# LA_16CH.net
KiCad netlist of a schematic drawn in EAGLE
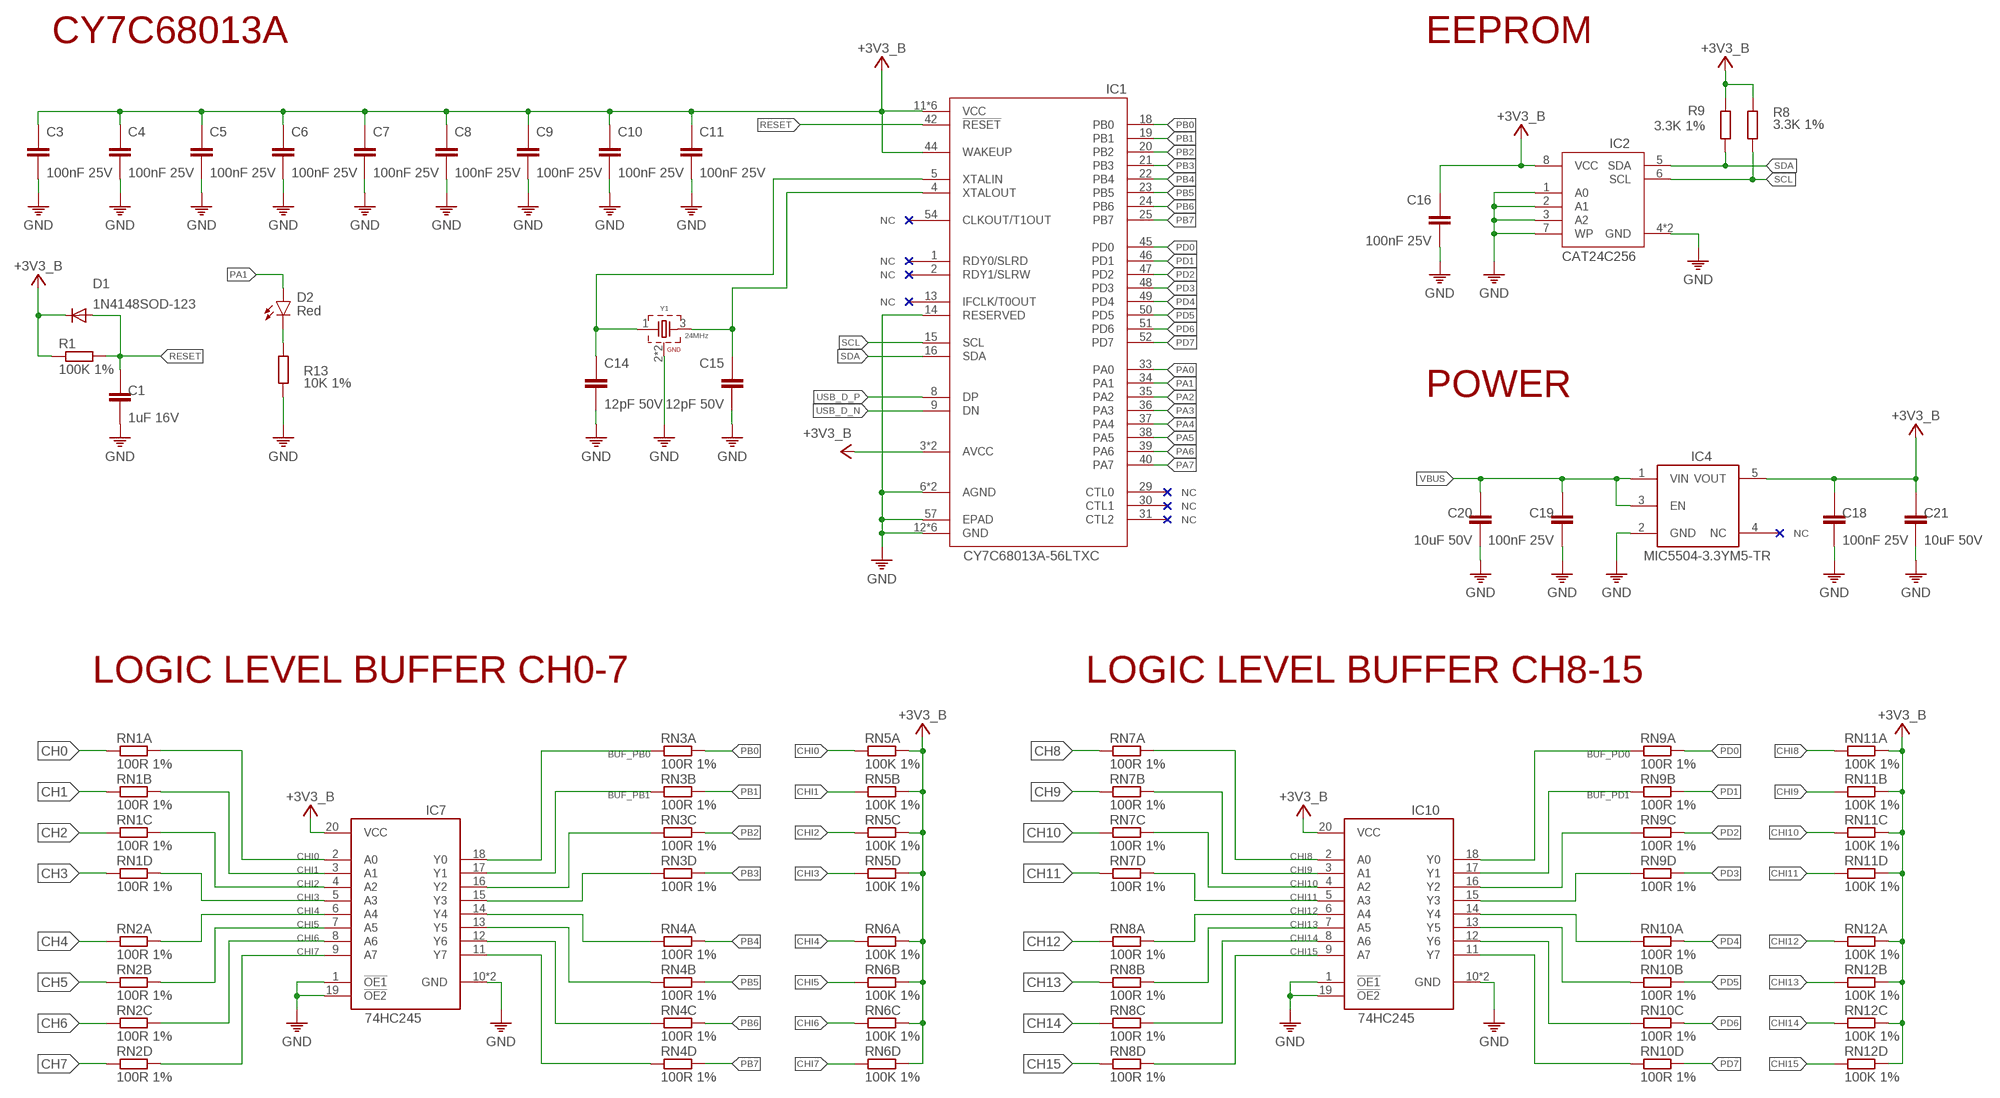
[diagram p0: schematic, sheet 1]

(export (version "E")
  (design (tool "Eeschema 10.0.6"))
  (components
    (comp (ref "C1")
      (value "1uF 16V")
      (footprint "eagle-import:0201")
      (fields (field (name "LCSC_PART") "C307385"))
      (libsource (lib "eagle-import") (part "1UF-16V0201"))
    )
    (comp (ref "C3")
      (value "100nF 25V")
      (footprint "eagle-import:0201")
      (fields (field (name "LCSC_PART") "C76939"))
      (libsource (lib "eagle-import") (part "100NF-25V-0201"))
    )
    (comp (ref "C4")
      (value "100nF 25V")
      (footprint "eagle-import:0201")
      (fields (field (name "LCSC_PART") "C76939"))
      (libsource (lib "eagle-import") (part "100NF-25V-0201"))
    )
    (comp (ref "C5")
      (value "100nF 25V")
      (footprint "eagle-import:0201")
      (fields (field (name "LCSC_PART") "C76939"))
      (libsource (lib "eagle-import") (part "100NF-25V-0201"))
    )
    (comp (ref "C6")
      (value "100nF 25V")
      (footprint "eagle-import:0201")
      (fields (field (name "LCSC_PART") "C76939"))
      (libsource (lib "eagle-import") (part "100NF-25V-0201"))
    )
    (comp (ref "C7")
      (value "100nF 25V")
      (footprint "eagle-import:0201")
      (fields (field (name "LCSC_PART") "C76939"))
      (libsource (lib "eagle-import") (part "100NF-25V-0201"))
    )
    (comp (ref "C8")
      (value "100nF 25V")
      (footprint "eagle-import:0201")
      (fields (field (name "LCSC_PART") "C76939"))
      (libsource (lib "eagle-import") (part "100NF-25V-0201"))
    )
    (comp (ref "C9")
      (value "100nF 25V")
      (footprint "eagle-import:0201")
      (fields (field (name "LCSC_PART") "C76939"))
      (libsource (lib "eagle-import") (part "100NF-25V-0201"))
    )
    (comp (ref "C10")
      (value "100nF 25V")
      (footprint "eagle-import:0201")
      (fields (field (name "LCSC_PART") "C76939"))
      (libsource (lib "eagle-import") (part "100NF-25V-0201"))
    )
    (comp (ref "C11")
      (value "100nF 25V")
      (footprint "eagle-import:0201")
      (fields (field (name "LCSC_PART") "C76939"))
      (libsource (lib "eagle-import") (part "100NF-25V-0201"))
    )
    (comp (ref "C14")
      (value "12pF 50V")
      (footprint "eagle-import:0201")
      (fields (field (name "LCSC_PART") "C50391"))
      (libsource (lib "eagle-import") (part "12PF-50V0201"))
    )
    (comp (ref "C15")
      (value "12pF 50V")
      (footprint "eagle-import:0201")
      (fields (field (name "LCSC_PART") "C50391"))
      (libsource (lib "eagle-import") (part "12PF-50V0201"))
    )
    (comp (ref "C16")
      (value "100nF 25V")
      (footprint "eagle-import:0201")
      (fields (field (name "LCSC_PART") "C76939"))
      (libsource (lib "eagle-import") (part "100NF-25V-0201"))
    )
    (comp (ref "C18")
      (value "100nF 25V")
      (footprint "eagle-import:0201")
      (fields (field (name "LCSC_PART") "C76939"))
      (libsource (lib "eagle-import") (part "100NF-25V-0201"))
    )
    (comp (ref "C19")
      (value "100nF 25V")
      (footprint "eagle-import:0201")
      (fields (field (name "LCSC_PART") "C76939"))
      (libsource (lib "eagle-import") (part "100NF-25V-0201"))
    )
    (comp (ref "C20")
      (value "10uF 50V")
      (footprint "eagle-import:0805")
      (fields (field (name "LCSC_PART") "C440198"))
      (libsource (lib "eagle-import") (part "10UF-50V-0805"))
    )
    (comp (ref "C21")
      (value "10uF 50V")
      (footprint "eagle-import:0805")
      (fields (field (name "LCSC_PART") "C440198"))
      (libsource (lib "eagle-import") (part "10UF-50V-0805"))
    )
    (comp (ref "D1")
      (value "1N4148SOD-123")
      (footprint "eagle-import:SOD-123FL")
      (libsource (lib "eagle-import") (part "DIODE_SOD-123FL"))
    )
    (comp (ref "D2")
      (value "Red")
      (footprint "eagle-import:LED-0603")
      (fields (field (name "LCSC_PART") "C2286"))
      (libsource (lib "eagle-import") (part "LED-REDLED-0603"))
    )
    (comp (ref "IC1")
      (value "CY7C68013A-56LTXC")
      (footprint "eagle-import:QFN50P800X800X100-57T665")
      (libsource (lib "eagle-import") (part "CY7C68013A-56QFNLFXC"))
    )
    (comp (ref "IC2")
      (value "CAT24C256HU4IGT3")
      (footprint "eagle-import:SON50P300X200X50-9T130X140N")
      (libsource (lib "eagle-import") (part "CAT24C256-HU4"))
    )
    (comp (ref "IC4")
      (value "MIC5504-3.3YM5-TR")
      (footprint "eagle-import:SOT23-5")
      (libsource (lib "eagle-import") (part "MIC5504-3.3YM5-TR"))
    )
    (comp (ref "IC7")
      (value "SN74LVC541ARGYR")
      (footprint "eagle-import:QFN50P350X450X100-25T305X205N")
      (libsource (lib "eagle-import") (part "74LVC541A"))
    )
    (comp (ref "IC10")
      (value "SN74LVC541ARGYR")
      (footprint "eagle-import:QFN50P350X450X100-25T305X205N")
      (libsource (lib "eagle-import") (part "74LVC541A"))
    )
    (comp (ref "R1")
      (value "100K 1%")
      (footprint "eagle-import:0201")
      (fields (field (name "LCSC_PART") "C270364"))
      (libsource (lib "eagle-import") (part "100K-1%0201"))
    )
    (comp (ref "R8")
      (value "3.3K 1%")
      (footprint "eagle-import:0201")
      (fields (field (name "LCSC_PART") "C270350"))
      (libsource (lib "eagle-import") (part "3.3K-1%0201"))
    )
    (comp (ref "R9")
      (value "3.3K 1%")
      (footprint "eagle-import:0201")
      (fields (field (name "LCSC_PART") "C270350"))
      (libsource (lib "eagle-import") (part "3.3K-1%0201"))
    )
    (comp (ref "R13")
      (value "10K 1%")
      (footprint "eagle-import:0603")
      (fields (field (name "LCSC_PART") "C25804"))
      (libsource (lib "eagle-import") (part "10K-1%0603"))
    )
    (comp (ref "RN1")
      (value "100R 1%")
      (footprint "eagle-import:0603X4-1206")
      (fields (field (name "LCSC_PART") "C136838"))
      (libsource (lib "eagle-import") (part "100R-1%_ARRAY0603X4-1206"))
    )
    (comp (ref "RN2")
      (value "100R 1%")
      (footprint "eagle-import:0603X4-1206")
      (fields (field (name "LCSC_PART") "C136838"))
      (libsource (lib "eagle-import") (part "100R-1%_ARRAY0603X4-1206"))
    )
    (comp (ref "RN3")
      (value "100R 1%")
      (footprint "eagle-import:0603X4-1206")
      (fields (field (name "LCSC_PART") "C136838"))
      (libsource (lib "eagle-import") (part "100R-1%_ARRAY0603X4-1206"))
    )
    (comp (ref "RN4")
      (value "100R 1%")
      (footprint "eagle-import:0603X4-1206")
      (fields (field (name "LCSC_PART") "C136838"))
      (libsource (lib "eagle-import") (part "100R-1%_ARRAY0603X4-1206"))
    )
    (comp (ref "RN5")
      (value "100K 1%")
      (footprint "eagle-import:0603X4-1206")
      (fields (field (name "LCSC_PART") "C110374"))
      (libsource (lib "eagle-import") (part "100K-1%_ARRAY0603X4-1206"))
    )
    (comp (ref "RN6")
      (value "100K 1%")
      (footprint "eagle-import:0603X4-1206")
      (fields (field (name "LCSC_PART") "C110374"))
      (libsource (lib "eagle-import") (part "100K-1%_ARRAY0603X4-1206"))
    )
    (comp (ref "RN7")
      (value "100R 1%")
      (footprint "eagle-import:0603X4-1206")
      (fields (field (name "LCSC_PART") "C136838"))
      (libsource (lib "eagle-import") (part "100R-1%_ARRAY0603X4-1206"))
    )
    (comp (ref "RN8")
      (value "100R 1%")
      (footprint "eagle-import:0603X4-1206")
      (fields (field (name "LCSC_PART") "C136838"))
      (libsource (lib "eagle-import") (part "100R-1%_ARRAY0603X4-1206"))
    )
    (comp (ref "RN9")
      (value "100R 1%")
      (footprint "eagle-import:0603X4-1206")
      (fields (field (name "LCSC_PART") "C136838"))
      (libsource (lib "eagle-import") (part "100R-1%_ARRAY0603X4-1206"))
    )
    (comp (ref "RN10")
      (value "100R 1%")
      (footprint "eagle-import:0603X4-1206")
      (fields (field (name "LCSC_PART") "C136838"))
      (libsource (lib "eagle-import") (part "100R-1%_ARRAY0603X4-1206"))
    )
    (comp (ref "RN11")
      (value "100K 1%")
      (footprint "eagle-import:0603X4-1206")
      (fields (field (name "LCSC_PART") "C110374"))
      (libsource (lib "eagle-import") (part "100K-1%_ARRAY0603X4-1206"))
    )
    (comp (ref "RN12")
      (value "100K 1%")
      (footprint "eagle-import:0603X4-1206")
      (fields (field (name "LCSC_PART") "C110374"))
      (libsource (lib "eagle-import") (part "100K-1%_ARRAY0603X4-1206"))
    )
    (comp (ref "Y1")
      (value "24MHz")
      (footprint "eagle-import:WE-XTAL_CFPX-180")
      (fields (field (name "TOLERANCE") "±10ppm"))
      (libsource (lib "eagle-import") (part "WE-XTAL_CFPX-180_830058149"))
    )
  )
  (nets
    (net (code "1") (name "+3V3_B") (class "Default")
      (node (ref "C10") (pin "1") (pinfunction "1_1") (pintype "passive"))
      (node (ref "C11") (pin "1") (pinfunction "1_1") (pintype "passive"))
      (node (ref "C16") (pin "1") (pinfunction "1_1") (pintype "passive"))
      (node (ref "C18") (pin "1") (pinfunction "1_1") (pintype "passive"))
      (node (ref "C21") (pin "1") (pinfunction "1_1") (pintype "passive"))
      (node (ref "C3") (pin "1") (pinfunction "1_1") (pintype "passive"))
      (node (ref "C4") (pin "1") (pinfunction "1_1") (pintype "passive"))
      (node (ref "C5") (pin "1") (pinfunction "1_1") (pintype "passive"))
      (node (ref "C6") (pin "1") (pinfunction "1_1") (pintype "passive"))
      (node (ref "C7") (pin "1") (pinfunction "1_1") (pintype "passive"))
      (node (ref "C8") (pin "1") (pinfunction "1_1") (pintype "passive"))
      (node (ref "C9") (pin "1") (pinfunction "1_1") (pintype "passive"))
      (node (ref "D1") (pin "C") (pinfunction "C_C") (pintype "passive"))
      (node (ref "IC1") (pin "11") (pinfunction "VCC_11") (pintype "power_in"))
      (node (ref "IC1") (pin "17") (pinfunction "VCC_17") (pintype "power_in"))
      (node (ref "IC1") (pin "27") (pinfunction "VCC_27") (pintype "power_in"))
      (node (ref "IC1") (pin "3") (pinfunction "AVCC_3") (pintype "power_in"))
      (node (ref "IC1") (pin "32") (pinfunction "VCC_32") (pintype "power_in"))
      (node (ref "IC1") (pin "43") (pinfunction "VCC_43") (pintype "power_in"))
      (node (ref "IC1") (pin "44") (pinfunction "WAKEUP_44") (pintype "input"))
      (node (ref "IC1") (pin "55") (pinfunction "VCC_55") (pintype "power_in"))
      (node (ref "IC1") (pin "7") (pinfunction "AVCC_7") (pintype "power_in"))
      (node (ref "IC10") (pin "20") (pinfunction "VCC_20") (pintype "power_in"))
      (node (ref "IC2") (pin "8") (pinfunction "VCC_8") (pintype "power_in"))
      (node (ref "IC4") (pin "5") (pinfunction "VOUT_5") (pintype "bidirectional"))
      (node (ref "IC7") (pin "20") (pinfunction "VCC_20") (pintype "power_in"))
      (node (ref "R1") (pin "1") (pinfunction "1_1") (pintype "passive"))
      (node (ref "R8") (pin "2") (pinfunction "2_2") (pintype "passive"))
      (node (ref "R9") (pin "2") (pinfunction "2_2") (pintype "passive"))
      (node (ref "RN11") (pin "A2") (pinfunction "2_A2") (pintype "passive"))
      (node (ref "RN11") (pin "B2") (pinfunction "2_B2") (pintype "passive"))
      (node (ref "RN11") (pin "C2") (pinfunction "2_C2") (pintype "passive"))
      (node (ref "RN11") (pin "D2") (pinfunction "2_D2") (pintype "passive"))
      (node (ref "RN12") (pin "A2") (pinfunction "2_A2") (pintype "passive"))
      (node (ref "RN12") (pin "B2") (pinfunction "2_B2") (pintype "passive"))
      (node (ref "RN12") (pin "C2") (pinfunction "2_C2") (pintype "passive"))
      (node (ref "RN12") (pin "D2") (pinfunction "2_D2") (pintype "passive"))
      (node (ref "RN5") (pin "A2") (pinfunction "2_A2") (pintype "passive"))
      (node (ref "RN5") (pin "B2") (pinfunction "2_B2") (pintype "passive"))
      (node (ref "RN5") (pin "C2") (pinfunction "2_C2") (pintype "passive"))
      (node (ref "RN5") (pin "D2") (pinfunction "2_D2") (pintype "passive"))
      (node (ref "RN6") (pin "A2") (pinfunction "2_A2") (pintype "passive"))
      (node (ref "RN6") (pin "B2") (pinfunction "2_B2") (pintype "passive"))
      (node (ref "RN6") (pin "C2") (pinfunction "2_C2") (pintype "passive"))
      (node (ref "RN6") (pin "D2") (pinfunction "2_D2") (pintype "passive"))
    )
    (net (code "2") (name "/BUF_PB0") (class "Default")
      (node (ref "IC7") (pin "18") (pinfunction "Y0_18") (pintype "bidirectional"))
      (node (ref "RN3") (pin "A1") (pinfunction "1_A1") (pintype "passive"))
    )
    (net (code "3") (name "/BUF_PB1") (class "Default")
      (node (ref "IC7") (pin "17") (pinfunction "Y1_17") (pintype "bidirectional"))
      (node (ref "RN3") (pin "B1") (pinfunction "1_B1") (pintype "passive"))
    )
    (net (code "4") (name "/BUF_PD0") (class "Default")
      (node (ref "IC10") (pin "18") (pinfunction "Y0_18") (pintype "bidirectional"))
      (node (ref "RN9") (pin "A1") (pinfunction "1_A1") (pintype "passive"))
    )
    (net (code "5") (name "/BUF_PD1") (class "Default")
      (node (ref "IC10") (pin "17") (pinfunction "Y1_17") (pintype "bidirectional"))
      (node (ref "RN9") (pin "B1") (pinfunction "1_B1") (pintype "passive"))
    )
    (net (code "6") (name "CH0") (class "Default")
      (node (ref "RN1") (pin "A1") (pinfunction "1_A1") (pintype "passive"))
    )
    (net (code "7") (name "CH1") (class "Default")
      (node (ref "RN1") (pin "B1") (pinfunction "1_B1") (pintype "passive"))
    )
    (net (code "8") (name "CH2") (class "Default")
      (node (ref "RN1") (pin "C1") (pinfunction "1_C1") (pintype "passive"))
    )
    (net (code "9") (name "CH3") (class "Default")
      (node (ref "RN1") (pin "D1") (pinfunction "1_D1") (pintype "passive"))
    )
    (net (code "10") (name "CH4") (class "Default")
      (node (ref "RN2") (pin "A1") (pinfunction "1_A1") (pintype "passive"))
    )
    (net (code "11") (name "CH5") (class "Default")
      (node (ref "RN2") (pin "B1") (pinfunction "1_B1") (pintype "passive"))
    )
    (net (code "12") (name "CH6") (class "Default")
      (node (ref "RN2") (pin "C1") (pinfunction "1_C1") (pintype "passive"))
    )
    (net (code "13") (name "CH7") (class "Default")
      (node (ref "RN2") (pin "D1") (pinfunction "1_D1") (pintype "passive"))
    )
    (net (code "14") (name "CH8") (class "Default")
      (node (ref "RN7") (pin "A1") (pinfunction "1_A1") (pintype "passive"))
    )
    (net (code "15") (name "CH9") (class "Default")
      (node (ref "RN7") (pin "B1") (pinfunction "1_B1") (pintype "passive"))
    )
    (net (code "16") (name "CH10") (class "Default")
      (node (ref "RN7") (pin "C1") (pinfunction "1_C1") (pintype "passive"))
    )
    (net (code "17") (name "CH11") (class "Default")
      (node (ref "RN7") (pin "D1") (pinfunction "1_D1") (pintype "passive"))
    )
    (net (code "18") (name "CH12") (class "Default")
      (node (ref "RN8") (pin "A1") (pinfunction "1_A1") (pintype "passive"))
    )
    (net (code "19") (name "CH13") (class "Default")
      (node (ref "RN8") (pin "B1") (pinfunction "1_B1") (pintype "passive"))
    )
    (net (code "20") (name "CH14") (class "Default")
      (node (ref "RN8") (pin "C1") (pinfunction "1_C1") (pintype "passive"))
    )
    (net (code "21") (name "CH15") (class "Default")
      (node (ref "RN8") (pin "D1") (pinfunction "1_D1") (pintype "passive"))
    )
    (net (code "22") (name "CHI0") (class "Default")
      (node (ref "IC7") (pin "2") (pinfunction "A0_2") (pintype "bidirectional"))
      (node (ref "RN1") (pin "A2") (pinfunction "2_A2") (pintype "passive"))
      (node (ref "RN5") (pin "A1") (pinfunction "1_A1") (pintype "passive"))
    )
    (net (code "23") (name "CHI1") (class "Default")
      (node (ref "IC7") (pin "3") (pinfunction "A1_3") (pintype "bidirectional"))
      (node (ref "RN1") (pin "B2") (pinfunction "2_B2") (pintype "passive"))
      (node (ref "RN5") (pin "B1") (pinfunction "1_B1") (pintype "passive"))
    )
    (net (code "24") (name "CHI2") (class "Default")
      (node (ref "IC7") (pin "4") (pinfunction "A2_4") (pintype "bidirectional"))
      (node (ref "RN1") (pin "C2") (pinfunction "2_C2") (pintype "passive"))
      (node (ref "RN5") (pin "C1") (pinfunction "1_C1") (pintype "passive"))
    )
    (net (code "25") (name "CHI3") (class "Default")
      (node (ref "IC7") (pin "5") (pinfunction "A3_5") (pintype "bidirectional"))
      (node (ref "RN1") (pin "D2") (pinfunction "2_D2") (pintype "passive"))
      (node (ref "RN5") (pin "D1") (pinfunction "1_D1") (pintype "passive"))
    )
    (net (code "26") (name "CHI4") (class "Default")
      (node (ref "IC7") (pin "6") (pinfunction "A4_6") (pintype "bidirectional"))
      (node (ref "RN2") (pin "A2") (pinfunction "2_A2") (pintype "passive"))
      (node (ref "RN6") (pin "A1") (pinfunction "1_A1") (pintype "passive"))
    )
    (net (code "27") (name "CHI5") (class "Default")
      (node (ref "IC7") (pin "7") (pinfunction "A5_7") (pintype "bidirectional"))
      (node (ref "RN2") (pin "B2") (pinfunction "2_B2") (pintype "passive"))
      (node (ref "RN6") (pin "B1") (pinfunction "1_B1") (pintype "passive"))
    )
    (net (code "28") (name "CHI6") (class "Default")
      (node (ref "IC7") (pin "8") (pinfunction "A6_8") (pintype "bidirectional"))
      (node (ref "RN2") (pin "C2") (pinfunction "2_C2") (pintype "passive"))
      (node (ref "RN6") (pin "C1") (pinfunction "1_C1") (pintype "passive"))
    )
    (net (code "29") (name "CHI7") (class "Default")
      (node (ref "IC7") (pin "9") (pinfunction "A7_9") (pintype "bidirectional"))
      (node (ref "RN2") (pin "D2") (pinfunction "2_D2") (pintype "passive"))
      (node (ref "RN6") (pin "D1") (pinfunction "1_D1") (pintype "passive"))
    )
    (net (code "30") (name "CHI8") (class "Default")
      (node (ref "IC10") (pin "2") (pinfunction "A0_2") (pintype "bidirectional"))
      (node (ref "RN11") (pin "A1") (pinfunction "1_A1") (pintype "passive"))
      (node (ref "RN7") (pin "A2") (pinfunction "2_A2") (pintype "passive"))
    )
    (net (code "31") (name "CHI9") (class "Default")
      (node (ref "IC10") (pin "3") (pinfunction "A1_3") (pintype "bidirectional"))
      (node (ref "RN11") (pin "B1") (pinfunction "1_B1") (pintype "passive"))
      (node (ref "RN7") (pin "B2") (pinfunction "2_B2") (pintype "passive"))
    )
    (net (code "32") (name "CHI10") (class "Default")
      (node (ref "IC10") (pin "4") (pinfunction "A2_4") (pintype "bidirectional"))
      (node (ref "RN11") (pin "C1") (pinfunction "1_C1") (pintype "passive"))
      (node (ref "RN7") (pin "C2") (pinfunction "2_C2") (pintype "passive"))
    )
    (net (code "33") (name "CHI11") (class "Default")
      (node (ref "IC10") (pin "5") (pinfunction "A3_5") (pintype "bidirectional"))
      (node (ref "RN11") (pin "D1") (pinfunction "1_D1") (pintype "passive"))
      (node (ref "RN7") (pin "D2") (pinfunction "2_D2") (pintype "passive"))
    )
    (net (code "34") (name "CHI12") (class "Default")
      (node (ref "IC10") (pin "6") (pinfunction "A4_6") (pintype "bidirectional"))
      (node (ref "RN12") (pin "A1") (pinfunction "1_A1") (pintype "passive"))
      (node (ref "RN8") (pin "A2") (pinfunction "2_A2") (pintype "passive"))
    )
    (net (code "35") (name "CHI13") (class "Default")
      (node (ref "IC10") (pin "7") (pinfunction "A5_7") (pintype "bidirectional"))
      (node (ref "RN12") (pin "B1") (pinfunction "1_B1") (pintype "passive"))
      (node (ref "RN8") (pin "B2") (pinfunction "2_B2") (pintype "passive"))
    )
    (net (code "36") (name "CHI14") (class "Default")
      (node (ref "IC10") (pin "8") (pinfunction "A6_8") (pintype "bidirectional"))
      (node (ref "RN12") (pin "C1") (pinfunction "1_C1") (pintype "passive"))
      (node (ref "RN8") (pin "C2") (pinfunction "2_C2") (pintype "passive"))
    )
    (net (code "37") (name "CHI15") (class "Default")
      (node (ref "IC10") (pin "9") (pinfunction "A7_9") (pintype "bidirectional"))
      (node (ref "RN12") (pin "D1") (pinfunction "1_D1") (pintype "passive"))
      (node (ref "RN8") (pin "D2") (pinfunction "2_D2") (pintype "passive"))
    )
    (net (code "38") (name "GND") (class "Default")
      (node (ref "C1") (pin "2") (pinfunction "2_2") (pintype "passive"))
      (node (ref "C10") (pin "2") (pinfunction "2_2") (pintype "passive"))
      (node (ref "C11") (pin "2") (pinfunction "2_2") (pintype "passive"))
      (node (ref "C14") (pin "2") (pinfunction "2_2") (pintype "passive"))
      (node (ref "C15") (pin "2") (pinfunction "2_2") (pintype "passive"))
      (node (ref "C16") (pin "2") (pinfunction "2_2") (pintype "passive"))
      (node (ref "C18") (pin "2") (pinfunction "2_2") (pintype "passive"))
      (node (ref "C19") (pin "2") (pinfunction "2_2") (pintype "passive"))
      (node (ref "C20") (pin "2") (pinfunction "2_2") (pintype "passive"))
      (node (ref "C21") (pin "2") (pinfunction "2_2") (pintype "passive"))
      (node (ref "C3") (pin "2") (pinfunction "2_2") (pintype "passive"))
      (node (ref "C4") (pin "2") (pinfunction "2_2") (pintype "passive"))
      (node (ref "C5") (pin "2") (pinfunction "2_2") (pintype "passive"))
      (node (ref "C6") (pin "2") (pinfunction "2_2") (pintype "passive"))
      (node (ref "C7") (pin "2") (pinfunction "2_2") (pintype "passive"))
      (node (ref "C8") (pin "2") (pinfunction "2_2") (pintype "passive"))
      (node (ref "C9") (pin "2") (pinfunction "2_2") (pintype "passive"))
      (node (ref "IC1") (pin "10") (pinfunction "AGND_10") (pintype "power_in"))
      (node (ref "IC1") (pin "12") (pinfunction "GND_12") (pintype "power_in"))
      (node (ref "IC1") (pin "14") (pinfunction "RESERVED_14") (pintype "bidirectional"))
      (node (ref "IC1") (pin "26") (pinfunction "GND_26") (pintype "power_in"))
      (node (ref "IC1") (pin "28") (pinfunction "GND_28") (pintype "power_in"))
      (node (ref "IC1") (pin "41") (pinfunction "GND_41") (pintype "power_in"))
      (node (ref "IC1") (pin "53") (pinfunction "GND_53") (pintype "power_in"))
      (node (ref "IC1") (pin "56") (pinfunction "GND_56") (pintype "power_in"))
      (node (ref "IC1") (pin "57") (pinfunction "EPAD_57") (pintype "power_in"))
      (node (ref "IC1") (pin "6") (pinfunction "AGND_6") (pintype "power_in"))
      (node (ref "IC10") (pin "1") (pinfunction "~{OE1}_1") (pintype "input"))
      (node (ref "IC10") (pin "10") (pinfunction "GND_10") (pintype "power_in"))
      (node (ref "IC10") (pin "19") (pinfunction "~{OE2}_19") (pintype "input"))
      (node (ref "IC10") (pin "PAD") (pinfunction "GND_PAD") (pintype "power_in"))
      (node (ref "IC2") (pin "1") (pinfunction "A0_1") (pintype "bidirectional"))
      (node (ref "IC2") (pin "2") (pinfunction "A1_2") (pintype "bidirectional"))
      (node (ref "IC2") (pin "3") (pinfunction "A2_3") (pintype "bidirectional"))
      (node (ref "IC2") (pin "4") (pinfunction "GND_4") (pintype "power_in"))
      (node (ref "IC2") (pin "7") (pinfunction "WP_7") (pintype "bidirectional"))
      (node (ref "IC2") (pin "9") (pinfunction "GND_9") (pintype "power_in"))
      (node (ref "IC4") (pin "2") (pinfunction "GND_2") (pintype "bidirectional"))
      (node (ref "IC7") (pin "1") (pinfunction "~{OE1}_1") (pintype "input"))
      (node (ref "IC7") (pin "10") (pinfunction "GND_10") (pintype "power_in"))
      (node (ref "IC7") (pin "19") (pinfunction "~{OE2}_19") (pintype "input"))
      (node (ref "IC7") (pin "PAD") (pinfunction "GND_PAD") (pintype "power_in"))
      (node (ref "R13") (pin "2") (pinfunction "2_2") (pintype "passive"))
      (node (ref "Y1") (pin "2") (pinfunction "GND_2") (pintype "passive"))
      (node (ref "Y1") (pin "4") (pinfunction "GND_4") (pintype "passive"))
    )
    (net (code "39") (name "Net-(D2-PadC)") (class "Default")
      (node (ref "D2") (pin "C") (pinfunction "C_C") (pintype "passive"))
      (node (ref "R13") (pin "1") (pinfunction "1_1") (pintype "passive"))
    )
    (net (code "40") (name "Net-(IC1-XTALIN)") (class "Default")
      (node (ref "C14") (pin "1") (pinfunction "1_1") (pintype "passive"))
      (node (ref "IC1") (pin "5") (pinfunction "XTALIN_5") (pintype "input"))
      (node (ref "Y1") (pin "1") (pinfunction "1_1") (pintype "passive"))
    )
    (net (code "41") (name "Net-(IC1-XTALOUT)") (class "Default")
      (node (ref "C15") (pin "1") (pinfunction "1_1") (pintype "passive"))
      (node (ref "IC1") (pin "4") (pinfunction "XTALOUT_4") (pintype "output"))
      (node (ref "Y1") (pin "3") (pinfunction "2_3") (pintype "passive"))
    )
    (net (code "42") (name "Net-(IC7-Y2)") (class "Default")
      (node (ref "IC7") (pin "16") (pinfunction "Y2_16") (pintype "bidirectional"))
      (node (ref "RN3") (pin "C1") (pinfunction "1_C1") (pintype "passive"))
    )
    (net (code "43") (name "Net-(IC7-Y3)") (class "Default")
      (node (ref "IC7") (pin "15") (pinfunction "Y3_15") (pintype "bidirectional"))
      (node (ref "RN3") (pin "D1") (pinfunction "1_D1") (pintype "passive"))
    )
    (net (code "44") (name "Net-(IC7-Y4)") (class "Default")
      (node (ref "IC7") (pin "14") (pinfunction "Y4_14") (pintype "bidirectional"))
      (node (ref "RN4") (pin "A1") (pinfunction "1_A1") (pintype "passive"))
    )
    (net (code "45") (name "Net-(IC7-Y5)") (class "Default")
      (node (ref "IC7") (pin "13") (pinfunction "Y5_13") (pintype "bidirectional"))
      (node (ref "RN4") (pin "B1") (pinfunction "1_B1") (pintype "passive"))
    )
    (net (code "46") (name "Net-(IC7-Y6)") (class "Default")
      (node (ref "IC7") (pin "12") (pinfunction "Y6_12") (pintype "bidirectional"))
      (node (ref "RN4") (pin "C1") (pinfunction "1_C1") (pintype "passive"))
    )
    (net (code "47") (name "Net-(IC7-Y7)") (class "Default")
      (node (ref "IC7") (pin "11") (pinfunction "Y7_11") (pintype "bidirectional"))
      (node (ref "RN4") (pin "D1") (pinfunction "1_D1") (pintype "passive"))
    )
    (net (code "48") (name "Net-(IC10-Y2)") (class "Default")
      (node (ref "IC10") (pin "16") (pinfunction "Y2_16") (pintype "bidirectional"))
      (node (ref "RN9") (pin "C1") (pinfunction "1_C1") (pintype "passive"))
    )
    (net (code "49") (name "Net-(IC10-Y3)") (class "Default")
      (node (ref "IC10") (pin "15") (pinfunction "Y3_15") (pintype "bidirectional"))
      (node (ref "RN9") (pin "D1") (pinfunction "1_D1") (pintype "passive"))
    )
    (net (code "50") (name "Net-(IC10-Y4)") (class "Default")
      (node (ref "IC10") (pin "14") (pinfunction "Y4_14") (pintype "bidirectional"))
      (node (ref "RN10") (pin "A1") (pinfunction "1_A1") (pintype "passive"))
    )
    (net (code "51") (name "Net-(IC10-Y5)") (class "Default")
      (node (ref "IC10") (pin "13") (pinfunction "Y5_13") (pintype "bidirectional"))
      (node (ref "RN10") (pin "B1") (pinfunction "1_B1") (pintype "passive"))
    )
    (net (code "52") (name "Net-(IC10-Y6)") (class "Default")
      (node (ref "IC10") (pin "12") (pinfunction "Y6_12") (pintype "bidirectional"))
      (node (ref "RN10") (pin "C1") (pinfunction "1_C1") (pintype "passive"))
    )
    (net (code "53") (name "Net-(IC10-Y7)") (class "Default")
      (node (ref "IC10") (pin "11") (pinfunction "Y7_11") (pintype "bidirectional"))
      (node (ref "RN10") (pin "D1") (pinfunction "1_D1") (pintype "passive"))
    )
    (net (code "54") (name "PA0") (class "Default")
      (node (ref "IC1") (pin "33") (pinfunction "PA0_33") (pintype "bidirectional"))
    )
    (net (code "55") (name "PA1") (class "Default")
      (node (ref "D2") (pin "A") (pinfunction "A_A") (pintype "passive"))
      (node (ref "IC1") (pin "34") (pinfunction "PA1_34") (pintype "bidirectional"))
    )
    (net (code "56") (name "PA2") (class "Default")
      (node (ref "IC1") (pin "35") (pinfunction "PA2_35") (pintype "bidirectional"))
    )
    (net (code "57") (name "PA3") (class "Default")
      (node (ref "IC1") (pin "36") (pinfunction "PA3_36") (pintype "bidirectional"))
    )
    (net (code "58") (name "PA4") (class "Default")
      (node (ref "IC1") (pin "37") (pinfunction "PA4_37") (pintype "bidirectional"))
    )
    (net (code "59") (name "PA5") (class "Default")
      (node (ref "IC1") (pin "38") (pinfunction "PA5_38") (pintype "bidirectional"))
    )
    (net (code "60") (name "PA6") (class "Default")
      (node (ref "IC1") (pin "39") (pinfunction "PA6_39") (pintype "bidirectional"))
    )
    (net (code "61") (name "PA7") (class "Default")
      (node (ref "IC1") (pin "40") (pinfunction "PA7_40") (pintype "bidirectional"))
    )
    (net (code "62") (name "PB0") (class "Default")
      (node (ref "IC1") (pin "18") (pinfunction "PB0_18") (pintype "bidirectional"))
      (node (ref "RN3") (pin "A2") (pinfunction "2_A2") (pintype "passive"))
    )
    (net (code "63") (name "PB1") (class "Default")
      (node (ref "IC1") (pin "19") (pinfunction "PB1_19") (pintype "bidirectional"))
      (node (ref "RN3") (pin "B2") (pinfunction "2_B2") (pintype "passive"))
    )
    (net (code "64") (name "PB2") (class "Default")
      (node (ref "IC1") (pin "20") (pinfunction "PB2_20") (pintype "bidirectional"))
      (node (ref "RN3") (pin "C2") (pinfunction "2_C2") (pintype "passive"))
    )
    (net (code "65") (name "PB3") (class "Default")
      (node (ref "IC1") (pin "21") (pinfunction "PB3_21") (pintype "bidirectional"))
      (node (ref "RN3") (pin "D2") (pinfunction "2_D2") (pintype "passive"))
    )
    (net (code "66") (name "PB4") (class "Default")
      (node (ref "IC1") (pin "22") (pinfunction "PB4_22") (pintype "bidirectional"))
      (node (ref "RN4") (pin "A2") (pinfunction "2_A2") (pintype "passive"))
    )
    (net (code "67") (name "PB5") (class "Default")
      (node (ref "IC1") (pin "23") (pinfunction "PB5_23") (pintype "bidirectional"))
      (node (ref "RN4") (pin "B2") (pinfunction "2_B2") (pintype "passive"))
    )
    (net (code "68") (name "PB6") (class "Default")
      (node (ref "IC1") (pin "24") (pinfunction "PB6_24") (pintype "bidirectional"))
      (node (ref "RN4") (pin "C2") (pinfunction "2_C2") (pintype "passive"))
    )
    (net (code "69") (name "PB7") (class "Default")
      (node (ref "IC1") (pin "25") (pinfunction "PB7_25") (pintype "bidirectional"))
      (node (ref "RN4") (pin "D2") (pinfunction "2_D2") (pintype "passive"))
    )
    (net (code "70") (name "PD0") (class "Default")
      (node (ref "IC1") (pin "45") (pinfunction "PD0_45") (pintype "bidirectional"))
      (node (ref "RN9") (pin "A2") (pinfunction "2_A2") (pintype "passive"))
    )
    (net (code "71") (name "PD1") (class "Default")
      (node (ref "IC1") (pin "46") (pinfunction "PD1_46") (pintype "bidirectional"))
      (node (ref "RN9") (pin "B2") (pinfunction "2_B2") (pintype "passive"))
    )
    (net (code "72") (name "PD2") (class "Default")
      (node (ref "IC1") (pin "47") (pinfunction "PD2_47") (pintype "bidirectional"))
      (node (ref "RN9") (pin "C2") (pinfunction "2_C2") (pintype "passive"))
    )
    (net (code "73") (name "PD3") (class "Default")
      (node (ref "IC1") (pin "48") (pinfunction "PD3_48") (pintype "bidirectional"))
      (node (ref "RN9") (pin "D2") (pinfunction "2_D2") (pintype "passive"))
    )
    (net (code "74") (name "PD4") (class "Default")
      (node (ref "IC1") (pin "49") (pinfunction "PD4_49") (pintype "bidirectional"))
      (node (ref "RN10") (pin "A2") (pinfunction "2_A2") (pintype "passive"))
    )
    (net (code "75") (name "PD5") (class "Default")
      (node (ref "IC1") (pin "50") (pinfunction "PD5_50") (pintype "bidirectional"))
      (node (ref "RN10") (pin "B2") (pinfunction "2_B2") (pintype "passive"))
    )
    (net (code "76") (name "PD6") (class "Default")
      (node (ref "IC1") (pin "51") (pinfunction "PD6_51") (pintype "bidirectional"))
      (node (ref "RN10") (pin "C2") (pinfunction "2_C2") (pintype "passive"))
    )
    (net (code "77") (name "PD7") (class "Default")
      (node (ref "IC1") (pin "52") (pinfunction "PD7_52") (pintype "bidirectional"))
      (node (ref "RN10") (pin "D2") (pinfunction "2_D2") (pintype "passive"))
    )
    (net (code "78") (name "RESET") (class "Default")
      (node (ref "C1") (pin "1") (pinfunction "1_1") (pintype "passive"))
      (node (ref "D1") (pin "A") (pinfunction "A_A") (pintype "passive"))
      (node (ref "IC1") (pin "42") (pinfunction "~{RESET}_42") (pintype "input"))
      (node (ref "R1") (pin "2") (pinfunction "2_2") (pintype "passive"))
    )
    (net (code "79") (name "SCL") (class "Default")
      (node (ref "IC1") (pin "15") (pinfunction "SCL_15") (pintype "bidirectional"))
      (node (ref "IC2") (pin "6") (pinfunction "SCL_6") (pintype "bidirectional"))
      (node (ref "R8") (pin "1") (pinfunction "1_1") (pintype "passive"))
    )
    (net (code "80") (name "SDA") (class "Default")
      (node (ref "IC1") (pin "16") (pinfunction "SDA_16") (pintype "bidirectional"))
      (node (ref "IC2") (pin "5") (pinfunction "SDA_5") (pintype "bidirectional"))
      (node (ref "R9") (pin "1") (pinfunction "1_1") (pintype "passive"))
    )
    (net (code "81") (name "USB_D_N") (class "Default")
      (node (ref "IC1") (pin "9") (pinfunction "DN_9") (pintype "bidirectional"))
    )
    (net (code "82") (name "USB_D_P") (class "Default")
      (node (ref "IC1") (pin "8") (pinfunction "DP_8") (pintype "bidirectional"))
    )
    (net (code "83") (name "VBUS") (class "Default")
      (node (ref "C19") (pin "1") (pinfunction "1_1") (pintype "passive"))
      (node (ref "C20") (pin "1") (pinfunction "1_1") (pintype "passive"))
      (node (ref "IC4") (pin "1") (pinfunction "VIN_1") (pintype "bidirectional"))
      (node (ref "IC4") (pin "3") (pinfunction "EN_3") (pintype "bidirectional"))
    )
    (net (code "84") (name "unconnected-(IC1-CLKOUT{slash}T1OUT-Pad54)") (class "Default")
      (node (ref "IC1") (pin "54") (pinfunction "CLKOUT/T1OUT_54") (pintype "bidirectional"))
    )
    (net (code "85") (name "unconnected-(IC1-CTL0-Pad29)") (class "Default")
      (node (ref "IC1") (pin "29") (pinfunction "CTL0_29") (pintype "bidirectional"))
    )
    (net (code "86") (name "unconnected-(IC1-CTL1-Pad30)") (class "Default")
      (node (ref "IC1") (pin "30") (pinfunction "CTL1_30") (pintype "bidirectional"))
    )
    (net (code "87") (name "unconnected-(IC1-CTL2-Pad31)") (class "Default")
      (node (ref "IC1") (pin "31") (pinfunction "CTL2_31") (pintype "bidirectional"))
    )
    (net (code "88") (name "unconnected-(IC1-IFCLK{slash}T0OUT-Pad13)") (class "Default")
      (node (ref "IC1") (pin "13") (pinfunction "IFCLK/T0OUT_13") (pintype "bidirectional"))
    )
    (net (code "89") (name "unconnected-(IC1-RDY0{slash}SLRD-Pad1)") (class "Default")
      (node (ref "IC1") (pin "1") (pinfunction "RDY0/SLRD_1") (pintype "bidirectional"))
    )
    (net (code "90") (name "unconnected-(IC1-RDY1{slash}SLRW-Pad2)") (class "Default")
      (node (ref "IC1") (pin "2") (pinfunction "RDY1/SLRW_2") (pintype "bidirectional"))
    )
    (net (code "91") (name "unconnected-(IC4-NC-Pad4)") (class "Default")
      (node (ref "IC4") (pin "4") (pinfunction "NC_4") (pintype "bidirectional"))
    )
  )
)
